# Sheet1_Etop12.net
KiCad netlist of a schematic drawn in Altium Designer
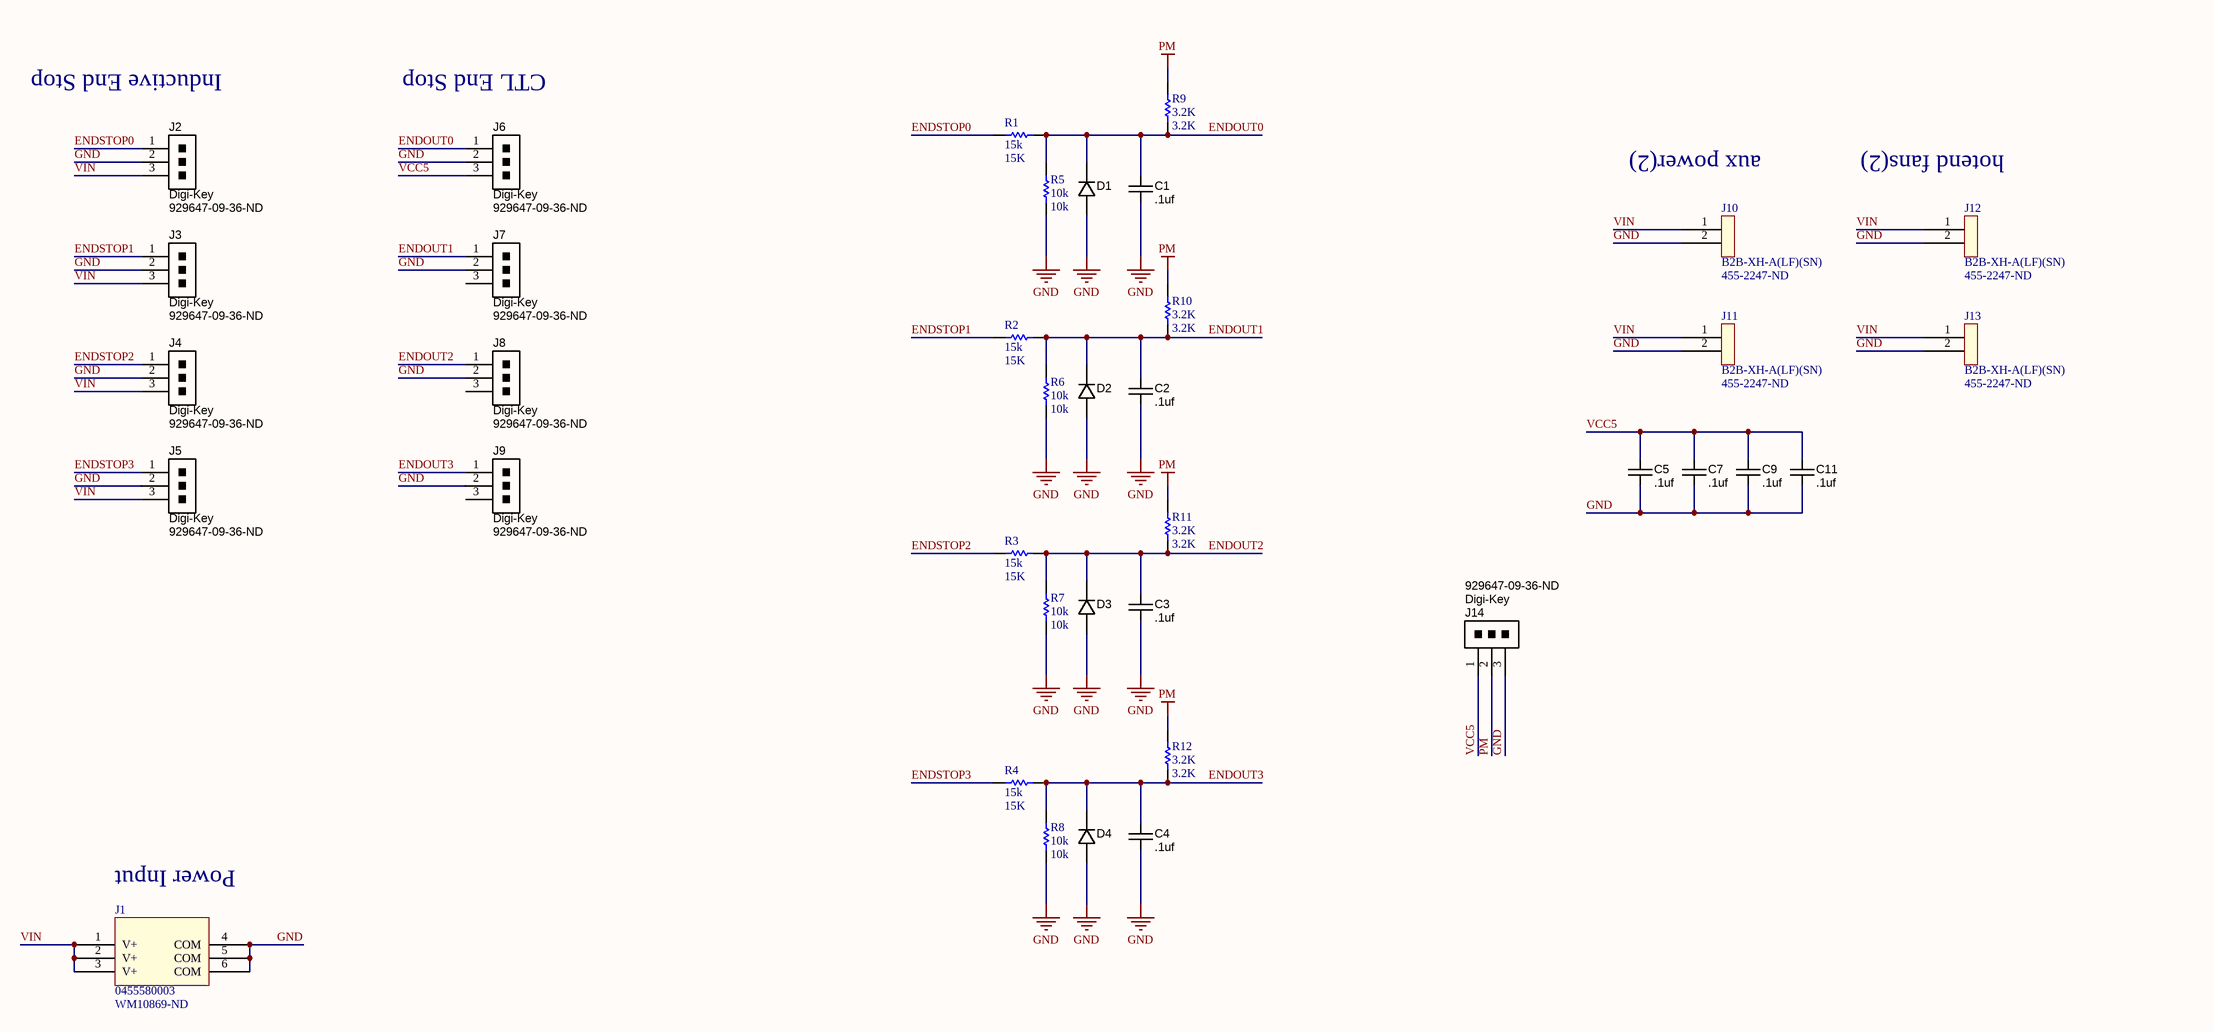
[diagram p0: Sheet1_Etop12.SchDoc]

(export (version "E")
  (design (tool "Eeschema 10.0.6"))
  (components
    (comp (ref "C1")
      (value ".1uf")
      (footprint "CAPC500P450250X550")
      (fields (field (name "TOLERANCE") "±10%") (field (name "Comment") "K104K10X7RF5UH5"))
      (libsource (lib "estop12") (part "K104K10X7RF5UH5"))
    )
    (comp (ref "C2")
      (value ".1uf")
      (footprint "CAPC500P450250X550")
      (fields (field (name "TOLERANCE") "±10%") (field (name "Comment") "K104K10X7RF5UH5"))
      (libsource (lib "estop12") (part "K104K10X7RF5UH5"))
    )
    (comp (ref "C3")
      (value ".1uf")
      (footprint "CAPC500P450250X550")
      (fields (field (name "TOLERANCE") "±10%") (field (name "Comment") "K104K10X7RF5UH5"))
      (libsource (lib "estop12") (part "K104K10X7RF5UH5"))
    )
    (comp (ref "C4")
      (value ".1uf")
      (footprint "CAPC500P450250X550")
      (fields (field (name "TOLERANCE") "±10%") (field (name "Comment") "K104K10X7RF5UH5"))
      (libsource (lib "estop12") (part "K104K10X7RF5UH5"))
    )
    (comp (ref "C5")
      (value ".1uf")
      (footprint "CAPC500P450250X550")
      (fields (field (name "TOLERANCE") "±10%") (field (name "Comment") "K104K10X7RF5UH5"))
      (libsource (lib "estop12") (part "K104K10X7RF5UH5"))
    )
    (comp (ref "C7")
      (value ".1uf")
      (footprint "CAPC500P450250X550")
      (fields (field (name "TOLERANCE") "±10%") (field (name "Comment") "K104K10X7RF5UH5"))
      (libsource (lib "estop12") (part "K104K10X7RF5UH5"))
    )
    (comp (ref "C9")
      (value ".1uf")
      (footprint "CAPC500P450250X550")
      (fields (field (name "TOLERANCE") "±10%") (field (name "Comment") "K104K10X7RF5UH5"))
      (libsource (lib "estop12") (part "K104K10X7RF5UH5"))
    )
    (comp (ref "C11")
      (value ".1uf")
      (footprint "CAPC500P450250X550")
      (fields (field (name "TOLERANCE") "±10%") (field (name "Comment") "K104K10X7RF5UH5"))
      (libsource (lib "estop12") (part "K104K10X7RF5UH5"))
    )
    (comp (ref "D1")
      (value "1N4733ATR")
      (footprint "DO-41")
      (description "DIODE ZENER 5.1V 1W DO41")
      (libsource (lib "estop12") (part "DIODE ZENER 5.1V 1W DO41"))
    )
    (comp (ref "D2")
      (value "1N4733ATR")
      (footprint "DO-41")
      (description "DIODE ZENER 5.1V 1W DO41")
      (libsource (lib "estop12") (part "DIODE ZENER 5.1V 1W DO41"))
    )
    (comp (ref "D3")
      (value "1N4733ATR")
      (footprint "DO-41")
      (description "DIODE ZENER 5.1V 1W DO41")
      (libsource (lib "estop12") (part "DIODE ZENER 5.1V 1W DO41"))
    )
    (comp (ref "D4")
      (value "1N4733ATR")
      (footprint "DO-41")
      (description "DIODE ZENER 5.1V 1W DO41")
      (libsource (lib "estop12") (part "DIODE ZENER 5.1V 1W DO41"))
    )
    (comp (ref "J1")
      (value "0455580003")
      (footprint "45558-NP")
      (fields (field (name "SUPPLIER PART NUMBER 1") "WM10869-ND"))
      (libsource (lib "fastcar") (part "0455580003"))
    )
    (comp (ref "J2")
      (value "CONN_HEADER_1x3P_0.100in")
      (footprint "1x3POS_HEADER")
      (description "Pin Header, THT, Single-row, 2.54mm pitch")
      (fields
        (field (name "SUPPLIER 1") "Digi-Key")
        (field (name "SUPPLIER PART NUMBER 1") "929647-09-36-ND")
      )
      (libsource (lib "PBL - Connectors") (part "CONN_HEADER_1x3P_0.100in"))
    )
    (comp (ref "J3")
      (value "CONN_HEADER_1x3P_0.100in")
      (footprint "1x3POS_HEADER")
      (description "Pin Header, THT, Single-row, 2.54mm pitch")
      (fields
        (field (name "SUPPLIER 1") "Digi-Key")
        (field (name "SUPPLIER PART NUMBER 1") "929647-09-36-ND")
      )
      (libsource (lib "PBL - Connectors") (part "CONN_HEADER_1x3P_0.100in"))
    )
    (comp (ref "J4")
      (value "CONN_HEADER_1x3P_0.100in")
      (footprint "1x3POS_HEADER")
      (description "Pin Header, THT, Single-row, 2.54mm pitch")
      (fields
        (field (name "SUPPLIER 1") "Digi-Key")
        (field (name "SUPPLIER PART NUMBER 1") "929647-09-36-ND")
      )
      (libsource (lib "PBL - Connectors") (part "CONN_HEADER_1x3P_0.100in"))
    )
    (comp (ref "J5")
      (value "CONN_HEADER_1x3P_0.100in")
      (footprint "1x3POS_HEADER")
      (description "Pin Header, THT, Single-row, 2.54mm pitch")
      (fields
        (field (name "SUPPLIER 1") "Digi-Key")
        (field (name "SUPPLIER PART NUMBER 1") "929647-09-36-ND")
      )
      (libsource (lib "PBL - Connectors") (part "CONN_HEADER_1x3P_0.100in"))
    )
    (comp (ref "J6")
      (value "CONN_HEADER_1x3P_0.100in")
      (footprint "1x3POS_HEADER")
      (description "Pin Header, THT, Single-row, 2.54mm pitch")
      (fields
        (field (name "SUPPLIER 1") "Digi-Key")
        (field (name "SUPPLIER PART NUMBER 1") "929647-09-36-ND")
      )
      (libsource (lib "PBL - Connectors") (part "CONN_HEADER_1x3P_0.100in"))
    )
    (comp (ref "J7")
      (value "CONN_HEADER_1x3P_0.100in")
      (footprint "1x3POS_HEADER")
      (description "Pin Header, THT, Single-row, 2.54mm pitch")
      (fields
        (field (name "SUPPLIER 1") "Digi-Key")
        (field (name "SUPPLIER PART NUMBER 1") "929647-09-36-ND")
      )
      (libsource (lib "PBL - Connectors") (part "CONN_HEADER_1x3P_0.100in"))
    )
    (comp (ref "J8")
      (value "CONN_HEADER_1x3P_0.100in")
      (footprint "1x3POS_HEADER")
      (description "Pin Header, THT, Single-row, 2.54mm pitch")
      (fields
        (field (name "SUPPLIER 1") "Digi-Key")
        (field (name "SUPPLIER PART NUMBER 1") "929647-09-36-ND")
      )
      (libsource (lib "PBL - Connectors") (part "CONN_HEADER_1x3P_0.100in"))
    )
    (comp (ref "J9")
      (value "CONN_HEADER_1x3P_0.100in")
      (footprint "1x3POS_HEADER")
      (description "Pin Header, THT, Single-row, 2.54mm pitch")
      (fields
        (field (name "SUPPLIER 1") "Digi-Key")
        (field (name "SUPPLIER PART NUMBER 1") "929647-09-36-ND")
      )
      (libsource (lib "PBL - Connectors") (part "CONN_HEADER_1x3P_0.100in"))
    )
    (comp (ref "J10")
      (value "B2B-XH-A(LF)(SN)")
      (footprint "77311-118-02LF")
      (description "CONN HEADER XH TOP 2POS 2.5MM  JST B2B-XH-A(LF)(SN)")
      (fields (field (name "SUPPLIER PART NUMBER 1") "455-2247-ND"))
      (libsource (lib "xbreak") (part "B2B-XH-A(LF)(SN)"))
    )
    (comp (ref "J11")
      (value "B2B-XH-A(LF)(SN)")
      (footprint "77311-118-02LF")
      (description "CONN HEADER XH TOP 2POS 2.5MM  JST B2B-XH-A(LF)(SN)")
      (fields (field (name "SUPPLIER PART NUMBER 1") "455-2247-ND"))
      (libsource (lib "xbreak") (part "B2B-XH-A(LF)(SN)"))
    )
    (comp (ref "J12")
      (value "B2B-XH-A(LF)(SN)")
      (footprint "77311-118-02LF")
      (description "CONN HEADER XH TOP 2POS 2.5MM  JST B2B-XH-A(LF)(SN)")
      (fields (field (name "SUPPLIER PART NUMBER 1") "455-2247-ND"))
      (libsource (lib "xbreak") (part "B2B-XH-A(LF)(SN)"))
    )
    (comp (ref "J13")
      (value "B2B-XH-A(LF)(SN)")
      (footprint "77311-118-02LF")
      (description "CONN HEADER XH TOP 2POS 2.5MM  JST B2B-XH-A(LF)(SN)")
      (fields (field (name "SUPPLIER PART NUMBER 1") "455-2247-ND"))
      (libsource (lib "xbreak") (part "B2B-XH-A(LF)(SN)"))
    )
    (comp (ref "J14")
      (value "CONN_HEADER_1x3P_0.100in")
      (footprint "1x3POS_HEADER")
      (description "Pin Header, THT, Single-row, 2.54mm pitch")
      (fields
        (field (name "SUPPLIER 1") "Digi-Key")
        (field (name "SUPPLIER PART NUMBER 1") "929647-09-36-ND")
      )
      (libsource (lib "") (part "CONN_HEADER_1x3P_0.100in_1"))
    )
    (comp (ref "R1")
      (value "15k")
      (footprint "AXIAL-0.3")
      (description "Resistor")
      (fields (field (name "ALTIUM_VALUE") "15K") (field (name "PUBLISHER") "Altium Limited"))
      (libsource (lib "Miscellaneous Devices") (part "Res1"))
    )
    (comp (ref "R2")
      (value "15k")
      (footprint "AXIAL-0.3")
      (description "Resistor")
      (fields (field (name "ALTIUM_VALUE") "15K") (field (name "PUBLISHER") "Altium Limited"))
      (libsource (lib "Miscellaneous Devices") (part "Res1"))
    )
    (comp (ref "R3")
      (value "15k")
      (footprint "AXIAL-0.3")
      (description "Resistor")
      (fields (field (name "ALTIUM_VALUE") "15K") (field (name "PUBLISHER") "Altium Limited"))
      (libsource (lib "Miscellaneous Devices") (part "Res1"))
    )
    (comp (ref "R4")
      (value "15k")
      (footprint "AXIAL-0.3")
      (description "Resistor")
      (fields (field (name "ALTIUM_VALUE") "15K") (field (name "PUBLISHER") "Altium Limited"))
      (libsource (lib "Miscellaneous Devices") (part "Res1"))
    )
    (comp (ref "R5")
      (value "10k")
      (footprint "AXIAL-0.3")
      (description "Resistor")
      (fields (field (name "ALTIUM_VALUE") "10k") (field (name "PUBLISHER") "Altium Limited"))
      (libsource (lib "Miscellaneous Devices") (part "Res1"))
    )
    (comp (ref "R6")
      (value "10k")
      (footprint "AXIAL-0.3")
      (description "Resistor")
      (fields (field (name "ALTIUM_VALUE") "10k") (field (name "PUBLISHER") "Altium Limited"))
      (libsource (lib "Miscellaneous Devices") (part "Res1"))
    )
    (comp (ref "R7")
      (value "10k")
      (footprint "AXIAL-0.3")
      (description "Resistor")
      (fields (field (name "ALTIUM_VALUE") "10k") (field (name "PUBLISHER") "Altium Limited"))
      (libsource (lib "Miscellaneous Devices") (part "Res1"))
    )
    (comp (ref "R8")
      (value "10k")
      (footprint "AXIAL-0.3")
      (description "Resistor")
      (fields (field (name "ALTIUM_VALUE") "10k") (field (name "PUBLISHER") "Altium Limited"))
      (libsource (lib "Miscellaneous Devices") (part "Res1"))
    )
    (comp (ref "R9")
      (value "3.2K")
      (footprint "AXIAL-0.3")
      (description "Resistor")
      (fields (field (name "ALTIUM_VALUE") "3.2K") (field (name "PUBLISHER") "Altium Limited"))
      (libsource (lib "Miscellaneous Devices") (part "Res1"))
    )
    (comp (ref "R10")
      (value "3.2K")
      (footprint "AXIAL-0.3")
      (description "Resistor")
      (fields (field (name "ALTIUM_VALUE") "3.2K") (field (name "PUBLISHER") "Altium Limited"))
      (libsource (lib "Miscellaneous Devices") (part "Res1"))
    )
    (comp (ref "R11")
      (value "3.2K")
      (footprint "AXIAL-0.3")
      (description "Resistor")
      (fields (field (name "ALTIUM_VALUE") "3.2K") (field (name "PUBLISHER") "Altium Limited"))
      (libsource (lib "Miscellaneous Devices") (part "Res1"))
    )
    (comp (ref "R12")
      (value "3.2K")
      (footprint "AXIAL-0.3")
      (description "Resistor")
      (fields (field (name "ALTIUM_VALUE") "3.2K") (field (name "PUBLISHER") "Altium Limited"))
      (libsource (lib "Miscellaneous Devices") (part "Res1"))
    )
  )
  (nets
    (net (code "1") (name "/ENDOUT0") (class "Default")
      (node (ref "C1") (pin "1") (pintype "passive"))
      (node (ref "D1") (pin "K") (pinfunction "K_K") (pintype "passive"))
      (node (ref "J6") (pin "1") (pinfunction "1_1") (pintype "passive"))
      (node (ref "R1") (pin "2") (pinfunction "2_2") (pintype "passive"))
      (node (ref "R5") (pin "2") (pinfunction "2_2") (pintype "passive"))
      (node (ref "R9") (pin "1") (pinfunction "1_1") (pintype "passive"))
    )
    (net (code "2") (name "/ENDOUT1") (class "Default")
      (node (ref "C2") (pin "1") (pintype "passive"))
      (node (ref "D2") (pin "K") (pinfunction "K_K") (pintype "passive"))
      (node (ref "J7") (pin "1") (pinfunction "1_1") (pintype "passive"))
      (node (ref "R10") (pin "1") (pinfunction "1_1") (pintype "passive"))
      (node (ref "R2") (pin "2") (pinfunction "2_2") (pintype "passive"))
      (node (ref "R6") (pin "2") (pinfunction "2_2") (pintype "passive"))
    )
    (net (code "3") (name "/ENDOUT2") (class "Default")
      (node (ref "C3") (pin "1") (pintype "passive"))
      (node (ref "D3") (pin "K") (pinfunction "K_K") (pintype "passive"))
      (node (ref "J8") (pin "1") (pinfunction "1_1") (pintype "passive"))
      (node (ref "R11") (pin "1") (pinfunction "1_1") (pintype "passive"))
      (node (ref "R3") (pin "2") (pinfunction "2_2") (pintype "passive"))
      (node (ref "R7") (pin "2") (pinfunction "2_2") (pintype "passive"))
    )
    (net (code "4") (name "/ENDOUT3") (class "Default")
      (node (ref "C4") (pin "1") (pintype "passive"))
      (node (ref "D4") (pin "K") (pinfunction "K_K") (pintype "passive"))
      (node (ref "J9") (pin "1") (pinfunction "1_1") (pintype "passive"))
      (node (ref "R12") (pin "1") (pinfunction "1_1") (pintype "passive"))
      (node (ref "R4") (pin "2") (pinfunction "2_2") (pintype "passive"))
      (node (ref "R8") (pin "2") (pinfunction "2_2") (pintype "passive"))
    )
    (net (code "5") (name "/ENDSTOP0") (class "Default")
      (node (ref "J2") (pin "1") (pinfunction "1_1") (pintype "passive"))
      (node (ref "R1") (pin "1") (pinfunction "1_1") (pintype "passive"))
    )
    (net (code "6") (name "/ENDSTOP1") (class "Default")
      (node (ref "J3") (pin "1") (pinfunction "1_1") (pintype "passive"))
      (node (ref "R2") (pin "1") (pinfunction "1_1") (pintype "passive"))
    )
    (net (code "7") (name "/ENDSTOP2") (class "Default")
      (node (ref "J4") (pin "1") (pinfunction "1_1") (pintype "passive"))
      (node (ref "R3") (pin "1") (pinfunction "1_1") (pintype "passive"))
    )
    (net (code "8") (name "/ENDSTOP3") (class "Default")
      (node (ref "J5") (pin "1") (pinfunction "1_1") (pintype "passive"))
      (node (ref "R4") (pin "1") (pinfunction "1_1") (pintype "passive"))
    )
    (net (code "9") (name "/VCC5") (class "Default")
      (node (ref "C11") (pin "1") (pintype "passive"))
      (node (ref "C5") (pin "1") (pintype "passive"))
      (node (ref "C7") (pin "1") (pintype "passive"))
      (node (ref "C9") (pin "1") (pintype "passive"))
      (node (ref "J14") (pin "1") (pinfunction "1_1") (pintype "passive"))
      (node (ref "J6") (pin "3") (pinfunction "3_3") (pintype "passive"))
    )
    (net (code "10") (name "/VIN") (class "Default")
      (node (ref "J1") (pin "1") (pinfunction "V+_1") (pintype "power_in"))
      (node (ref "J1") (pin "2") (pinfunction "V+_2") (pintype "power_in"))
      (node (ref "J1") (pin "3") (pinfunction "V+_3") (pintype "power_in"))
      (node (ref "J10") (pin "1") (pintype "passive"))
      (node (ref "J11") (pin "1") (pintype "passive"))
      (node (ref "J12") (pin "1") (pintype "passive"))
      (node (ref "J13") (pin "1") (pintype "passive"))
      (node (ref "J2") (pin "3") (pinfunction "3_3") (pintype "passive"))
      (node (ref "J3") (pin "3") (pinfunction "3_3") (pintype "passive"))
      (node (ref "J4") (pin "3") (pinfunction "3_3") (pintype "passive"))
      (node (ref "J5") (pin "3") (pinfunction "3_3") (pintype "passive"))
    )
    (net (code "11") (name "GND") (class "Default")
      (node (ref "C1") (pin "2") (pintype "passive"))
      (node (ref "C11") (pin "2") (pintype "passive"))
      (node (ref "C2") (pin "2") (pintype "passive"))
      (node (ref "C3") (pin "2") (pintype "passive"))
      (node (ref "C4") (pin "2") (pintype "passive"))
      (node (ref "C5") (pin "2") (pintype "passive"))
      (node (ref "C7") (pin "2") (pintype "passive"))
      (node (ref "C9") (pin "2") (pintype "passive"))
      (node (ref "D1") (pin "A") (pinfunction "A_A") (pintype "passive"))
      (node (ref "D2") (pin "A") (pinfunction "A_A") (pintype "passive"))
      (node (ref "D3") (pin "A") (pinfunction "A_A") (pintype "passive"))
      (node (ref "D4") (pin "A") (pinfunction "A_A") (pintype "passive"))
      (node (ref "J1") (pin "4") (pinfunction "COM_4") (pintype "power_in"))
      (node (ref "J1") (pin "5") (pinfunction "COM_5") (pintype "power_in"))
      (node (ref "J1") (pin "6") (pinfunction "COM_6") (pintype "power_in"))
      (node (ref "J10") (pin "2") (pintype "passive"))
      (node (ref "J11") (pin "2") (pintype "passive"))
      (node (ref "J12") (pin "2") (pintype "passive"))
      (node (ref "J13") (pin "2") (pintype "passive"))
      (node (ref "J14") (pin "3") (pinfunction "3_3") (pintype "passive"))
      (node (ref "J2") (pin "2") (pinfunction "2_2") (pintype "passive"))
      (node (ref "J3") (pin "2") (pinfunction "2_2") (pintype "passive"))
      (node (ref "J4") (pin "2") (pinfunction "2_2") (pintype "passive"))
      (node (ref "J5") (pin "2") (pinfunction "2_2") (pintype "passive"))
      (node (ref "J6") (pin "2") (pinfunction "2_2") (pintype "passive"))
      (node (ref "J7") (pin "2") (pinfunction "2_2") (pintype "passive"))
      (node (ref "J8") (pin "2") (pinfunction "2_2") (pintype "passive"))
      (node (ref "J9") (pin "2") (pinfunction "2_2") (pintype "passive"))
      (node (ref "R5") (pin "1") (pinfunction "1_1") (pintype "passive"))
      (node (ref "R6") (pin "1") (pinfunction "1_1") (pintype "passive"))
      (node (ref "R7") (pin "1") (pinfunction "1_1") (pintype "passive"))
      (node (ref "R8") (pin "1") (pinfunction "1_1") (pintype "passive"))
    )
    (net (code "12") (name "PM") (class "Default")
      (node (ref "J14") (pin "2") (pinfunction "2_2") (pintype "passive"))
      (node (ref "R10") (pin "2") (pinfunction "2_2") (pintype "passive"))
      (node (ref "R11") (pin "2") (pinfunction "2_2") (pintype "passive"))
      (node (ref "R12") (pin "2") (pinfunction "2_2") (pintype "passive"))
      (node (ref "R9") (pin "2") (pinfunction "2_2") (pintype "passive"))
    )
    (net (code "13") (name "unconnected-(J7-Pad3)") (class "Default")
      (node (ref "J7") (pin "3") (pinfunction "3_3") (pintype "passive"))
    )
    (net (code "14") (name "unconnected-(J8-Pad3)") (class "Default")
      (node (ref "J8") (pin "3") (pinfunction "3_3") (pintype "passive"))
    )
    (net (code "15") (name "unconnected-(J9-Pad3)") (class "Default")
      (node (ref "J9") (pin "3") (pinfunction "3_3") (pintype "passive"))
    )
  )
)
